# Connectors_and_PDB.net
KiCad netlist of a schematic drawn in Altium Designer
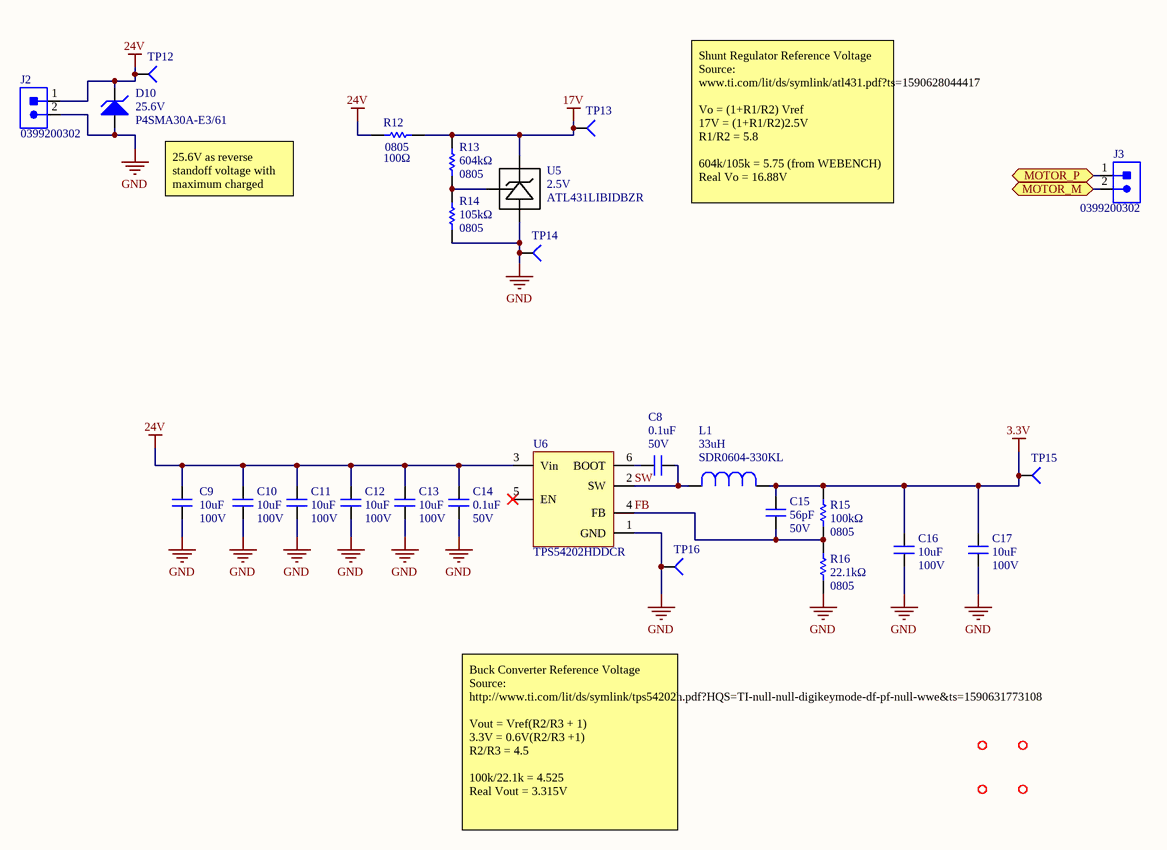
[diagram p0: Connectors and PDB.SchDoc]

(export (version "E")
  (design (tool "Eeschema 10.0.6"))
  (components
    (comp (ref "C8")
      (value "0.1uF")
      (footprint "CAPC2012X140N")
      (description "CAP CER 0.1UF 50V X7R 0805")
      (fields
        (field (name "TOLERANCE") "10%")
        (field (name "VOLTAGE RATING") "50V")
        (field (name "Comment") "CAP_0.1uF_50V_0805")
      )
      (libsource (lib "UWRT_Schematic_Library_2020") (part "CAP_0.1uF_50V_0805"))
    )
    (comp (ref "C9")
      (value "CAP_10uF_100V_1210")
      (footprint "CAPC1210(3225)")
      (description "CAP CER 10uF 100V X7S 10% 1210")
      (fields
        (field (name "TOLERANCE") "10%")
        (field (name "CAPACITANCE") "10uF")
        (field (name "VOLTAGE RATING") "100V")
      )
      (libsource (lib "UWRT_Schematic_Library_2020") (part "CAP_10uF_100V_1210"))
    )
    (comp (ref "C10")
      (value "CAP_10uF_100V_1210")
      (footprint "CAPC1210(3225)")
      (description "CAP CER 10uF 100V X7S 10% 1210")
      (fields
        (field (name "TOLERANCE") "10%")
        (field (name "CAPACITANCE") "10uF")
        (field (name "VOLTAGE RATING") "100V")
      )
      (libsource (lib "UWRT_Schematic_Library_2020") (part "CAP_10uF_100V_1210"))
    )
    (comp (ref "C11")
      (value "CAP_10uF_100V_1210")
      (footprint "CAPC1210(3225)")
      (description "CAP CER 10uF 100V X7S 10% 1210")
      (fields
        (field (name "TOLERANCE") "10%")
        (field (name "CAPACITANCE") "10uF")
        (field (name "VOLTAGE RATING") "100V")
      )
      (libsource (lib "UWRT_Schematic_Library_2020") (part "CAP_10uF_100V_1210"))
    )
    (comp (ref "C12")
      (value "CAP_10uF_100V_1210")
      (footprint "CAPC1210(3225)")
      (description "CAP CER 10uF 100V X7S 10% 1210")
      (fields
        (field (name "VOLTAGE RATING") "100V")
        (field (name "TOLERANCE") "10%")
        (field (name "CAPACITANCE") "10uF")
      )
      (libsource (lib "UWRT_Schematic_Library_2020") (part "CAP_10uF_100V_1210"))
    )
    (comp (ref "C13")
      (value "CAP_10uF_100V_1210")
      (footprint "CAPC1210(3225)")
      (description "CAP CER 10uF 100V X7S 10% 1210")
      (fields
        (field (name "VOLTAGE RATING") "100V")
        (field (name "TOLERANCE") "10%")
        (field (name "CAPACITANCE") "10uF")
      )
      (libsource (lib "UWRT_Schematic_Library_2020") (part "CAP_10uF_100V_1210"))
    )
    (comp (ref "C14")
      (value "0.1uF")
      (footprint "CAPC2012X140N")
      (description "CAP CER 0.1UF 50V X7R 0805")
      (fields
        (field (name "TOLERANCE") "10%")
        (field (name "VOLTAGE RATING") "50V")
        (field (name "Comment") "CAP_0.1uF_50V_0805")
      )
      (libsource (lib "UWRT_Schematic_Library_2020") (part "CAP_0.1uF_50V_0805"))
    )
    (comp (ref "C15")
      (value "CAP_56pF_50V_0805")
      (footprint "CAP 0805_2012")
      (description "CAP CER 56PF 50V C0G/NP0")
      (fields
        (field (name "TOLERANCE") "1%")
        (field (name "VOLTAGE RATING") "50V")
        (field (name "CAPACITANCE") "56pF")
      )
      (libsource (lib "UWRT_Schematic_Library_2020") (part "CAP_56pF_50V_0805"))
    )
    (comp (ref "C16")
      (value "CAP_10uF_100V_1210")
      (footprint "CAPC1210(3225)")
      (description "CAP CER 10uF 100V X7S 10% 1210")
      (fields
        (field (name "CAPACITANCE") "10uF")
        (field (name "TOLERANCE") "10%")
        (field (name "VOLTAGE RATING") "100V")
      )
      (libsource (lib "UWRT_Schematic_Library_2020") (part "CAP_10uF_100V_1210"))
    )
    (comp (ref "C17")
      (value "CAP_10uF_100V_1210")
      (footprint "CAPC1210(3225)")
      (description "CAP CER 10uF 100V X7S 10% 1210")
      (fields
        (field (name "CAPACITANCE") "10uF")
        (field (name "TOLERANCE") "10%")
        (field (name "VOLTAGE RATING") "100V")
      )
      (libsource (lib "UWRT_Schematic_Library_2020") (part "CAP_10uF_100V_1210"))
    )
    (comp (ref "D10")
      (value "P4SMA30A-E3/61")
      (footprint "DO-214AC_UNI")
      (description "TVS DIODE, 400W, 25.6V, UNI, DO-214AC")
      (fields
        (field (name "REVERSE STANDOFF VOLTAGE") "25.6V")
        (field (name "MANUFACTURER PART NUMBER 1") "P4SMA30A-E3/61")
      )
      (libsource (lib "UWRT_Schematic_Library_2020") (part "P4SMA30A-E3/61"))
    )
    (comp (ref "J2")
      (value "SCREW_TERM_115A")
      (footprint "MOLEX-0399200302")
      (description "CONN TERM BLOCK 2POS 15MM 1-8AWG")
      (fields (field (name "MANUFACTURER PART NUMBER 1") "0399200302") (field (name "VOLTAGE") "600V"))
      (libsource (lib "") (part "SCREW_TERM_115A_1"))
    )
    (comp (ref "J3")
      (value "SCREW_TERM_115A")
      (footprint "MOLEX-0399200302")
      (description "CONN TERM BLOCK 2POS 15MM 1-8AWG")
      (fields (field (name "MANUFACTURER PART NUMBER 1") "0399200302") (field (name "VOLTAGE") "600V"))
      (libsource (lib "UWRT_Schematic_Library_2020") (part "SCREW_TERM_115A"))
    )
    (comp (ref "L1")
      (value "IND_33uH_880mA")
      (footprint "IND_BOURNS_SDR0604")
      (description "IND, 33uH, 10%, 1 Element, Ferrite-Core, SMD")
      (fields
        (field (name "TOLERANCE") "10%")
        (field (name "MANUFACTURER PART NUMBER 1") "SDR0604-330KL")
        (field (name "INDUCTANCE") "33uH")
      )
      (libsource (lib "UWRT_Schematic_Library_2020") (part "IND_33uH_880mA"))
    )
    (comp (ref "MH1")
      (value "MOUNTING_HOLES")
      (footprint "MOUNTING_HOLE")
      (description "6cm x 6cm")
      (libsource (lib "UWRT_Schematic_Library_2020") (part "MOUNTING_HOLES"))
    )
    (comp (ref "MH2")
      (value "MOUNTING_HOLES")
      (footprint "MOUNTING_HOLE")
      (description "6cm x 6cm")
      (libsource (lib "UWRT_Schematic_Library_2020") (part "MOUNTING_HOLES"))
    )
    (comp (ref "MH3")
      (value "MOUNTING_HOLES")
      (footprint "MOUNTING_HOLE")
      (description "6cm x 6cm")
      (libsource (lib "UWRT_Schematic_Library_2020") (part "MOUNTING_HOLES"))
    )
    (comp (ref "MH4")
      (value "MOUNTING_HOLES")
      (footprint "MOUNTING_HOLE")
      (description "6cm x 6cm")
      (libsource (lib "UWRT_Schematic_Library_2020") (part "MOUNTING_HOLES"))
    )
    (comp (ref "R12")
      (value "100Ω")
      (footprint "RESC2012X60N")
      (description "RES SMD 100 OHM 1% 1/8W 0805")
      (fields (field (name "CASE CODE (IMPERIAL)") "0805") (field (name "Comment") "RES_100Ω_0805"))
      (libsource (lib "UWRT_Schematic_Library_2020") (part "RES_100Ω_0805"))
    )
    (comp (ref "R13")
      (value "RES_604kΩ_0805")
      (footprint "RESC2012X60N")
      (description "RES SMD 604K OHM 0.1% 1/4W 0805")
      (fields
        (field (name "TOLERANCE") "0.1%")
        (field (name "RESISTANCE") "604kΩ")
        (field (name "CASE/PACKAGE") "0805")
      )
      (libsource (lib "UWRT_Schematic_Library_2020") (part "RES_604kΩ_0805"))
    )
    (comp (ref "R14")
      (value "RES_105kΩ_0805")
      (footprint "RESC2012X60N")
      (description "RES SMD 105K OHM 0.1% 1/8W 0805")
      (fields
        (field (name "TOLERANCE") "0.1%")
        (field (name "RESISTANCE") "105kΩ")
        (field (name "CASE CODE (IMPERIAL)") "0805")
      )
      (libsource (lib "UWRT_Schematic_Library_2020") (part "RES_105kΩ_0805"))
    )
    (comp (ref "R15")
      (value "RES_100kΩ_0805")
      (footprint "RESC2012X60N")
      (description "RES SMD 100K OHM 0.5% 1/8W 0805")
      (fields
        (field (name "TOLERANCE") "0.5%")
        (field (name "RESISTANCE") "100kΩ")
        (field (name "CASE/PACKAGE") "0805")
      )
      (libsource (lib "UWRT_Schematic_Library_2020") (part "RES_100kΩ_0805"))
    )
    (comp (ref "R16")
      (value "RES_22.1kΩ_0805")
      (footprint "RESC2012X60N")
      (description "RES SMD 22.1K OHM 1% 1/8W 0805")
      (fields
        (field (name "TOLERANCE") "1%")
        (field (name "CASE CODE (IMPERIAL)") "0805")
        (field (name "RESISTANCE") "22.1kΩ")
      )
      (libsource (lib "UWRT_Schematic_Library_2020") (part "RES_22.1kΩ_0805"))
    )
    (comp (ref "TP12")
      (value "TESTPOINT_SMD")
      (footprint "TESTPOINT")
      (libsource (lib "UWRT_Schematic_Library_2020") (part "TESTPOINT_SMD"))
    )
    (comp (ref "TP13")
      (value "TESTPOINT_SMD")
      (footprint "TESTPOINT")
      (libsource (lib "UWRT_Schematic_Library_2020") (part "TESTPOINT_SMD"))
    )
    (comp (ref "TP14")
      (value "TESTPOINT_SMD")
      (footprint "TESTPOINT")
      (libsource (lib "UWRT_Schematic_Library_2020") (part "TESTPOINT_SMD"))
    )
    (comp (ref "TP15")
      (value "TESTPOINT_SMD")
      (footprint "TESTPOINT")
      (libsource (lib "UWRT_Schematic_Library_2020") (part "TESTPOINT_SMD"))
    )
    (comp (ref "TP16")
      (value "TESTPOINT_SMD")
      (footprint "TESTPOINT")
      (libsource (lib "UWRT_Schematic_Library_2020") (part "TESTPOINT_SMD"))
    )
    (comp (ref "U5")
      (value "ATL431LIBIDBZR")
      (footprint "SOT23-3")
      (description "Three Terminal Voltage Reference, 1 Output, 2.5V, Trim/Adjustable, PDSO3")
      (fields
        (field (name "REFERENCE VOLTAGE") "2.5V")
        (field (name "MANUFACTURER PART NUMBER 1") "ATL431LIBIDBZR")
      )
      (libsource (lib "UWRT_Schematic_Library_2020") (part "ATL431LIBIDBZR"))
    )
    (comp (ref "U6")
      (value "TPS54202HDDCR")
      (footprint "SOT23-6")
      (description "Switching Regulator, Current-mode, 3.9A, 500kHz Switching Freq-Max, PDSO6")
      (fields (field (name "MANUFACTURER PART NUMBER 1") "TPS54202HDDCR"))
      (libsource (lib "UWRT_Schematic_Library_2020") (part "TPS54202HDDCR"))
    )
  )
  (nets
    (net (code "1") (name "/FB") (class "Default")
      (node (ref "C15") (pin "1") (pinfunction "1_1") (pintype "passive"))
      (node (ref "R15") (pin "1") (pinfunction "1_1") (pintype "passive"))
      (node (ref "R16") (pin "2") (pinfunction "2_2") (pintype "passive"))
      (node (ref "U6") (pin "4") (pinfunction "FB_4") (pintype "passive"))
    )
    (net (code "2") (name "/MOTOR_M") (class "Default")
      (node (ref "J3") (pin "2") (pinfunction "2_2") (pintype "passive"))
    )
    (net (code "3") (name "/MOTOR_P") (class "Default")
      (node (ref "J3") (pin "1") (pinfunction "1_1") (pintype "passive"))
    )
    (net (code "4") (name "/SW") (class "Default")
      (node (ref "C8") (pin "2") (pinfunction "2_2") (pintype "passive"))
      (node (ref "L1") (pin "2") (pinfunction "2_2") (pintype "passive"))
      (node (ref "U6") (pin "2") (pinfunction "SW_2") (pintype "passive"))
    )
    (net (code "5") (name "3.3V") (class "Default")
      (node (ref "C15") (pin "2") (pinfunction "2_2") (pintype "passive"))
      (node (ref "C16") (pin "2") (pinfunction "2_2") (pintype "passive"))
      (node (ref "C17") (pin "2") (pinfunction "2_2") (pintype "passive"))
      (node (ref "L1") (pin "1") (pinfunction "1_1") (pintype "passive"))
      (node (ref "R15") (pin "2") (pinfunction "2_2") (pintype "passive"))
      (node (ref "TP15") (pin "1") (pinfunction "=value_1") (pintype "passive"))
    )
    (net (code "6") (name "17V") (class "Default")
      (node (ref "R12") (pin "2") (pinfunction "2_2") (pintype "passive"))
      (node (ref "R13") (pin "2") (pinfunction "2_2") (pintype "passive"))
      (node (ref "TP13") (pin "1") (pinfunction "=value_1") (pintype "passive"))
      (node (ref "U5") (pin "1") (pinfunction "CATHODE_1") (pintype "passive"))
    )
    (net (code "7") (name "24V") (class "Default")
      (node (ref "C10") (pin "2") (pinfunction "2_2") (pintype "passive"))
      (node (ref "C11") (pin "2") (pinfunction "2_2") (pintype "passive"))
      (node (ref "C12") (pin "2") (pinfunction "2_2") (pintype "passive"))
      (node (ref "C13") (pin "2") (pinfunction "2_2") (pintype "passive"))
      (node (ref "C14") (pin "2") (pinfunction "2_2") (pintype "passive"))
      (node (ref "C9") (pin "2") (pinfunction "2_2") (pintype "passive"))
      (node (ref "D10") (pin "2") (pinfunction "2_2") (pintype "passive"))
      (node (ref "J2") (pin "1") (pinfunction "1_1") (pintype "passive"))
      (node (ref "R12") (pin "1") (pinfunction "1_1") (pintype "passive"))
      (node (ref "TP12") (pin "1") (pinfunction "=value_1") (pintype "passive"))
      (node (ref "U6") (pin "3") (pinfunction "Vin_3") (pintype "passive"))
    )
    (net (code "8") (name "GND") (class "Default")
      (node (ref "C10") (pin "1") (pinfunction "1_1") (pintype "passive"))
      (node (ref "C11") (pin "1") (pinfunction "1_1") (pintype "passive"))
      (node (ref "C12") (pin "1") (pinfunction "1_1") (pintype "passive"))
      (node (ref "C13") (pin "1") (pinfunction "1_1") (pintype "passive"))
      (node (ref "C14") (pin "1") (pinfunction "1_1") (pintype "passive"))
      (node (ref "C16") (pin "1") (pinfunction "1_1") (pintype "passive"))
      (node (ref "C17") (pin "1") (pinfunction "1_1") (pintype "passive"))
      (node (ref "C9") (pin "1") (pinfunction "1_1") (pintype "passive"))
      (node (ref "D10") (pin "1") (pinfunction "1_1") (pintype "passive"))
      (node (ref "J2") (pin "2") (pinfunction "2_2") (pintype "passive"))
      (node (ref "R14") (pin "1") (pinfunction "1_1") (pintype "passive"))
      (node (ref "R16") (pin "1") (pinfunction "1_1") (pintype "passive"))
      (node (ref "TP14") (pin "1") (pinfunction "=value_1") (pintype "passive"))
      (node (ref "TP16") (pin "1") (pinfunction "=value_1") (pintype "passive"))
      (node (ref "U5") (pin "3") (pinfunction "ANODE_3") (pintype "passive"))
      (node (ref "U6") (pin "1") (pinfunction "GND_1") (pintype "passive"))
    )
    (net (code "9") (name "Net-(U5-REF)") (class "Default")
      (node (ref "R13") (pin "1") (pinfunction "1_1") (pintype "passive"))
      (node (ref "R14") (pin "2") (pinfunction "2_2") (pintype "passive"))
      (node (ref "U5") (pin "2") (pinfunction "REF_2") (pintype "passive"))
    )
    (net (code "10") (name "Net-(U6-BOOT)") (class "Default")
      (node (ref "C8") (pin "1") (pinfunction "1_1") (pintype "passive"))
      (node (ref "U6") (pin "6") (pinfunction "BOOT_6") (pintype "passive"))
    )
    (net (code "11") (name "unconnected-(U6-EN-Pad5)") (class "Default")
      (node (ref "U6") (pin "5") (pinfunction "EN_5") (pintype "passive+no_connect"))
    )
  )
)
